# Sheet3.net
KiCad netlist of a schematic drawn in Altium Designer
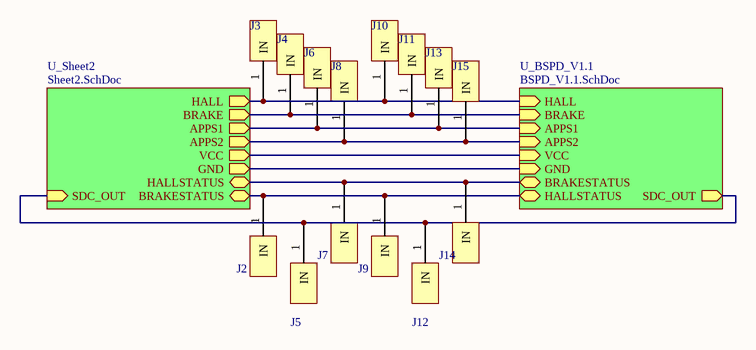
[diagram p0: Sheet3.SchDoc]

(export (version "E")
  (design (tool "Eeschema 10.0.6"))
  (components
    (comp (ref "J2")
      (value "22AWG JUMPER")
      (footprint "22 AWG Hole")
      (libsource (lib "") (part "22AWG JUMPER_1"))
    )
    (comp (ref "J3")
      (value "22AWG JUMPER")
      (footprint "22 AWG Hole")
      (libsource (lib "LF50ABDT-TRY") (part "22AWG JUMPER"))
    )
    (comp (ref "J4")
      (value "22AWG JUMPER")
      (footprint "22 AWG Hole")
      (libsource (lib "LF50ABDT-TRY") (part "22AWG JUMPER"))
    )
    (comp (ref "J5")
      (value "22AWG JUMPER")
      (footprint "22 AWG Hole")
      (libsource (lib "") (part "22AWG JUMPER_1"))
    )
    (comp (ref "J6")
      (value "22AWG JUMPER")
      (footprint "22 AWG Hole")
      (libsource (lib "LF50ABDT-TRY") (part "22AWG JUMPER"))
    )
    (comp (ref "J7")
      (value "22AWG JUMPER")
      (footprint "22 AWG Hole")
      (libsource (lib "") (part "22AWG JUMPER_1"))
    )
    (comp (ref "J8")
      (value "22AWG JUMPER")
      (footprint "22 AWG Hole")
      (libsource (lib "LF50ABDT-TRY") (part "22AWG JUMPER"))
    )
    (comp (ref "J9")
      (value "22AWG JUMPER")
      (footprint "22 AWG Hole")
      (libsource (lib "") (part "22AWG JUMPER_1"))
    )
    (comp (ref "J10")
      (value "22AWG JUMPER")
      (footprint "22 AWG Hole")
      (libsource (lib "LF50ABDT-TRY") (part "22AWG JUMPER"))
    )
    (comp (ref "J11")
      (value "22AWG JUMPER")
      (footprint "22 AWG Hole")
      (libsource (lib "LF50ABDT-TRY") (part "22AWG JUMPER"))
    )
    (comp (ref "J12")
      (value "22AWG JUMPER")
      (footprint "22 AWG Hole")
      (libsource (lib "") (part "22AWG JUMPER_1"))
    )
    (comp (ref "J13")
      (value "22AWG JUMPER")
      (footprint "22 AWG Hole")
      (libsource (lib "LF50ABDT-TRY") (part "22AWG JUMPER"))
    )
    (comp (ref "J14")
      (value "22AWG JUMPER")
      (footprint "22 AWG Hole")
      (libsource (lib "") (part "22AWG JUMPER_1"))
    )
    (comp (ref "J15")
      (value "22AWG JUMPER")
      (footprint "22 AWG Hole")
      (libsource (lib "LF50ABDT-TRY") (part "22AWG JUMPER"))
    )
  )
  (nets
    (net (code "1") (name "/APPS1") (class "Default")
      (node (ref "J13") (pin "1") (pinfunction "IN_1") (pintype "passive"))
      (node (ref "J6") (pin "1") (pinfunction "IN_1") (pintype "passive"))
    )
    (net (code "2") (name "/APPS2") (class "Default")
      (node (ref "J15") (pin "1") (pinfunction "IN_1") (pintype "passive"))
      (node (ref "J8") (pin "1") (pinfunction "IN_1") (pintype "passive"))
    )
    (net (code "3") (name "/BRAKE") (class "Default")
      (node (ref "J11") (pin "1") (pinfunction "IN_1") (pintype "passive"))
      (node (ref "J4") (pin "1") (pinfunction "IN_1") (pintype "passive"))
    )
    (net (code "4") (name "/BRAKESTATUS") (class "Default")
      (node (ref "J2") (pin "1") (pinfunction "IN_1") (pintype "passive"))
      (node (ref "J9") (pin "1") (pinfunction "IN_1") (pintype "passive"))
    )
    (net (code "5") (name "/BRAKESTATUS_1") (class "Default")
      (node (ref "J14") (pin "1") (pinfunction "IN_1") (pintype "passive"))
      (node (ref "J7") (pin "1") (pinfunction "IN_1") (pintype "passive"))
    )
    (net (code "7") (name "/HALL") (class "Default")
      (node (ref "J10") (pin "1") (pinfunction "IN_1") (pintype "passive"))
      (node (ref "J3") (pin "1") (pinfunction "IN_1") (pintype "passive"))
    )
    (net (code "8") (name "/SDC_OUT") (class "Default")
      (node (ref "J12") (pin "1") (pinfunction "IN_1") (pintype "passive"))
      (node (ref "J5") (pin "1") (pinfunction "IN_1") (pintype "passive"))
    )
  )
)
